# attenuverter_7-24-22.net
KiCad netlist of a schematic drawn in EAGLE
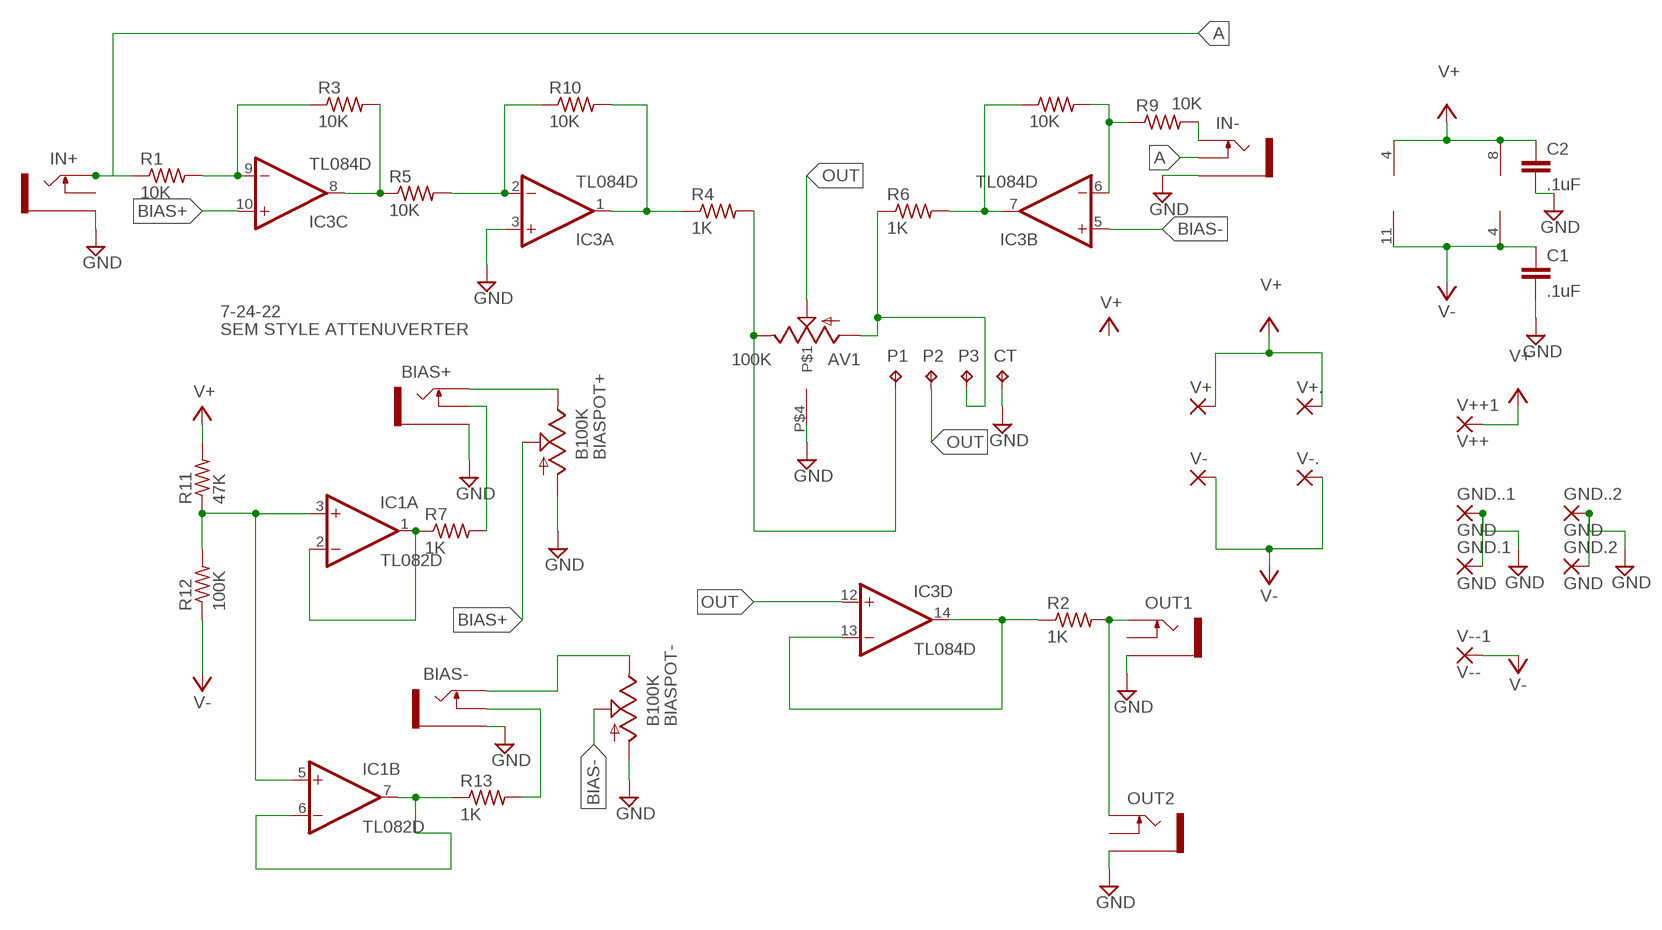
[diagram p0: schematic, sheet 1]

(export (version "E")
  (design (tool "Eeschema 10.0.6"))
  (components
    (comp (ref "AV1")
      (value "100K")
      (footprint "eagle-import:ALPSCENTERTAP")
      (libsource (lib "eagle-import") (part "ALPSRK11K114"))
    )
    (comp (ref "BIAS+")
      (value "THONKICONNOLD")
      (footprint "eagle-import:THONKICONN")
      (libsource (lib "eagle-import") (part "THONKICONNOLD"))
    )
    (comp (ref "BIAS-")
      (value "THONKICONNOLD")
      (footprint "eagle-import:THONKICONN")
      (libsource (lib "eagle-import") (part "THONKICONNOLD"))
    )
    (comp (ref "BIASPOT+")
      (value "B100K")
      (footprint "eagle-import:9MM_SNAP-IN_POT")
      (libsource (lib "eagle-import") (part "9MM_SNAP-IN_POT_"))
    )
    (comp (ref "BIASPOT-")
      (value "B100K")
      (footprint "eagle-import:9MM_SNAP-IN_POT")
      (libsource (lib "eagle-import") (part "9MM_SNAP-IN_POT_"))
    )
    (comp (ref "C1")
      (value ".1uF")
      (footprint "eagle-import:C5B3.5")
      (libsource (lib "eagle-import") (part "C5/3.5"))
    )
    (comp (ref "C2")
      (value ".1uF")
      (footprint "eagle-import:C5B3.5")
      (libsource (lib "eagle-import") (part "C5/3.5"))
    )
    (comp (ref "CT")
      (value "TPPAD1-13")
      (footprint "eagle-import:P1-13")
      (libsource (lib "eagle-import") (part "TPPAD1-13"))
    )
    (comp (ref "GND..1")
      (value "GND")
      (footprint "eagle-import:1,6_0,8")
      (libsource (lib "eagle-import") (part "1,6/0,8"))
    )
    (comp (ref "GND..2")
      (value "GND")
      (footprint "eagle-import:1,6_0,8")
      (libsource (lib "eagle-import") (part "1,6/0,8"))
    )
    (comp (ref "GND.1")
      (value "GND")
      (footprint "eagle-import:1,6_0,8")
      (libsource (lib "eagle-import") (part "1,6/0,8"))
    )
    (comp (ref "GND.2")
      (value "GND")
      (footprint "eagle-import:1,6_0,8")
      (libsource (lib "eagle-import") (part "1,6/0,8"))
    )
    (comp (ref "IC1")
      (value "TL082D")
      (footprint "eagle-import:SO08")
      (libsource (lib "eagle-import") (part "TL082D"))
    )
    (comp (ref "IC3")
      (value "TL084D")
      (footprint "eagle-import:SO14")
      (libsource (lib "eagle-import") (part "TL084D"))
    )
    (comp (ref "IN+")
      (value "THONKICONNOLD")
      (footprint "eagle-import:THONKICONN")
      (libsource (lib "eagle-import") (part "THONKICONNOLD"))
    )
    (comp (ref "IN-")
      (value "THONKICONNOLD")
      (footprint "eagle-import:THONKICONN")
      (libsource (lib "eagle-import") (part "THONKICONNOLD"))
    )
    (comp (ref "OUT1")
      (value "THONKICONNOLD")
      (footprint "eagle-import:THONKICONN")
      (libsource (lib "eagle-import") (part "THONKICONNOLD"))
    )
    (comp (ref "OUT2")
      (value "THONKICONNOLD")
      (footprint "eagle-import:THONKICONN")
      (libsource (lib "eagle-import") (part "THONKICONNOLD"))
    )
    (comp (ref "P1")
      (value "TPPAD1-13")
      (footprint "eagle-import:P1-13")
      (libsource (lib "eagle-import") (part "TPPAD1-13"))
    )
    (comp (ref "P2")
      (value "TPPAD1-13")
      (footprint "eagle-import:P1-13")
      (libsource (lib "eagle-import") (part "TPPAD1-13"))
    )
    (comp (ref "P3")
      (value "TPPAD1-13")
      (footprint "eagle-import:P1-13")
      (libsource (lib "eagle-import") (part "TPPAD1-13"))
    )
    (comp (ref "R1")
      (value "10K")
      (footprint "eagle-import:0204_7")
      (libsource (lib "eagle-import") (part "R-US_0204/7"))
    )
    (comp (ref "R2")
      (value "1K")
      (footprint "eagle-import:0204_7")
      (libsource (lib "eagle-import") (part "R-US_0204/7"))
    )
    (comp (ref "R3")
      (value "10K")
      (footprint "eagle-import:0204_7")
      (libsource (lib "eagle-import") (part "R-US_0204/7"))
    )
    (comp (ref "R4")
      (value "1K")
      (footprint "eagle-import:0204_7")
      (libsource (lib "eagle-import") (part "R-US_0204/7"))
    )
    (comp (ref "R5")
      (value "10K")
      (footprint "eagle-import:0204_7")
      (libsource (lib "eagle-import") (part "R-US_0204/7"))
    )
    (comp (ref "R6")
      (value "1K")
      (footprint "eagle-import:0204_7")
      (libsource (lib "eagle-import") (part "R-US_0204/7"))
    )
    (comp (ref "R7")
      (value "1K")
      (footprint "eagle-import:0204_7")
      (libsource (lib "eagle-import") (part "R-US_0204/7"))
    )
    (comp (ref "R8")
      (value "10K")
      (footprint "eagle-import:0204_7")
      (libsource (lib "eagle-import") (part "R-US_0204/7"))
    )
    (comp (ref "R9")
      (value "10K")
      (footprint "eagle-import:0204_7")
      (libsource (lib "eagle-import") (part "R-US_0204/7"))
    )
    (comp (ref "R10")
      (value "10K")
      (footprint "eagle-import:0204_7")
      (libsource (lib "eagle-import") (part "R-US_0204/7"))
    )
    (comp (ref "R11")
      (value "47K")
      (footprint "eagle-import:0204_7")
      (libsource (lib "eagle-import") (part "R-US_0204/7"))
    )
    (comp (ref "R12")
      (value "100K")
      (footprint "eagle-import:0204_7")
      (libsource (lib "eagle-import") (part "R-US_0204/7"))
    )
    (comp (ref "R13")
      (value "1K")
      (footprint "eagle-import:0204_7")
      (libsource (lib "eagle-import") (part "R-US_0204/7"))
    )
    (comp (ref "V+")
      (value "WIREPAD2,54/1,1")
      (footprint "eagle-import:2,54_1,1")
      (libsource (lib "eagle-import") (part "WIREPAD2,54/1,1"))
    )
    (comp (ref "V++1")
      (value "V++")
      (footprint "eagle-import:1,6_0,8")
      (libsource (lib "eagle-import") (part "1,6/0,8"))
    )
    (comp (ref "V+.")
      (value "WIREPAD2,54/1,1")
      (footprint "eagle-import:2,54_1,1")
      (libsource (lib "eagle-import") (part "WIREPAD2,54/1,1"))
    )
    (comp (ref "V-")
      (value "WIREPAD2,54/1,1")
      (footprint "eagle-import:2,54_1,1")
      (libsource (lib "eagle-import") (part "WIREPAD2,54/1,1"))
    )
    (comp (ref "V--1")
      (value "V--")
      (footprint "eagle-import:1,6_0,8")
      (libsource (lib "eagle-import") (part "1,6/0,8"))
    )
    (comp (ref "V-.")
      (value "WIREPAD2,54/1,1")
      (footprint "eagle-import:2,54_1,1")
      (libsource (lib "eagle-import") (part "WIREPAD2,54/1,1"))
    )
  )
  (nets
    (net (code "1") (name "A") (class "Default")
      (node (ref "IN+") (pin "P$3_TIP") (pinfunction "TIP_P$3_TIP") (pintype "passive"))
      (node (ref "IN-") (pin "P$2_SWITCH") (pinfunction "SWITCH_P$2_SWITCH") (pintype "passive"))
      (node (ref "R1") (pin "1") (pinfunction "1_1") (pintype "passive"))
    )
    (net (code "2") (name "BIAS+") (class "Default")
      (node (ref "BIASPOT+") (pin "2") (pinfunction "S_2") (pintype "passive"))
      (node (ref "IC3") (pin "10") (pinfunction "+IN_10") (pintype "input"))
    )
    (net (code "3") (name "BIAS-") (class "Default")
      (node (ref "BIASPOT-") (pin "2") (pinfunction "S_2") (pintype "passive"))
      (node (ref "IC3") (pin "5") (pinfunction "+IN_5") (pintype "input"))
    )
    (net (code "4") (name "GND") (class "Default")
      (node (ref "AV1") (pin "P$4") (pinfunction "P$1_P$4") (pintype "passive"))
      (node (ref "BIAS+") (pin "P$1_SLEEVE") (pinfunction "SLEEVE_P$1_SLEEVE") (pintype "passive"))
      (node (ref "BIAS-") (pin "P$1_SLEEVE") (pinfunction "SLEEVE_P$1_SLEEVE") (pintype "passive"))
      (node (ref "BIASPOT+") (pin "1") (pinfunction "A_1") (pintype "passive"))
      (node (ref "BIASPOT-") (pin "1") (pinfunction "A_1") (pintype "passive"))
      (node (ref "C1") (pin "2") (pinfunction "2_2") (pintype "passive"))
      (node (ref "C2") (pin "2") (pinfunction "2_2") (pintype "passive"))
      (node (ref "CT") (pin "TP") (pinfunction "TP_TP") (pintype "input"))
      (node (ref "GND..1") (pin "1") (pinfunction "P_1") (pintype "passive"))
      (node (ref "GND..2") (pin "1") (pinfunction "P_1") (pintype "passive"))
      (node (ref "GND.1") (pin "1") (pinfunction "P_1") (pintype "passive"))
      (node (ref "GND.2") (pin "1") (pinfunction "P_1") (pintype "passive"))
      (node (ref "IC3") (pin "3") (pinfunction "+IN_3") (pintype "input"))
      (node (ref "IN+") (pin "P$1_SLEEVE") (pinfunction "SLEEVE_P$1_SLEEVE") (pintype "passive"))
      (node (ref "IN-") (pin "P$1_SLEEVE") (pinfunction "SLEEVE_P$1_SLEEVE") (pintype "passive"))
      (node (ref "OUT1") (pin "P$1_SLEEVE") (pinfunction "SLEEVE_P$1_SLEEVE") (pintype "passive"))
      (node (ref "OUT2") (pin "P$1_SLEEVE") (pinfunction "SLEEVE_P$1_SLEEVE") (pintype "passive"))
    )
    (net (code "5") (name "Net-(AV1-HIGH)") (class "Default")
      (node (ref "AV1") (pin "P$1") (pinfunction "HIGH_P$1") (pintype "passive"))
      (node (ref "P1") (pin "TP") (pinfunction "TP_TP") (pintype "input"))
      (node (ref "R4") (pin "2") (pinfunction "2_2") (pintype "passive"))
    )
    (net (code "6") (name "Net-(AV1-LOW)") (class "Default")
      (node (ref "AV1") (pin "P$3") (pinfunction "LOW_P$3") (pintype "passive"))
      (node (ref "P3") (pin "TP") (pinfunction "TP_TP") (pintype "input"))
      (node (ref "R6") (pin "1") (pinfunction "1_1") (pintype "passive"))
    )
    (net (code "7") (name "Net-(BIAS+-SWITCH)") (class "Default")
      (node (ref "BIAS+") (pin "P$2_SWITCH") (pinfunction "SWITCH_P$2_SWITCH") (pintype "passive"))
      (node (ref "R7") (pin "2") (pinfunction "2_2") (pintype "passive"))
    )
    (net (code "8") (name "Net-(BIAS+-TIP)") (class "Default")
      (node (ref "BIAS+") (pin "P$3_TIP") (pinfunction "TIP_P$3_TIP") (pintype "passive"))
      (node (ref "BIASPOT+") (pin "3") (pinfunction "E_3") (pintype "passive"))
    )
    (net (code "9") (name "Net-(BIAS--SWITCH)") (class "Default")
      (node (ref "BIAS-") (pin "P$2_SWITCH") (pinfunction "SWITCH_P$2_SWITCH") (pintype "passive"))
      (node (ref "R13") (pin "2") (pinfunction "2_2") (pintype "passive"))
    )
    (net (code "10") (name "Net-(BIAS--TIP)") (class "Default")
      (node (ref "BIAS-") (pin "P$3_TIP") (pinfunction "TIP_P$3_TIP") (pintype "passive"))
      (node (ref "BIASPOT-") (pin "3") (pinfunction "E_3") (pintype "passive"))
    )
    (net (code "11") (name "Net-(IC1A-+IN)") (class "Default")
      (node (ref "IC1") (pin "3") (pinfunction "+IN_3") (pintype "input"))
      (node (ref "IC1") (pin "5") (pinfunction "+IN_5") (pintype "input"))
      (node (ref "R11") (pin "1") (pinfunction "1_1") (pintype "passive"))
      (node (ref "R12") (pin "2") (pinfunction "2_2") (pintype "passive"))
    )
    (net (code "12") (name "Net-(IC1A--IN)") (class "Default")
      (node (ref "IC1") (pin "1") (pinfunction "OUT_1") (pintype "output"))
      (node (ref "IC1") (pin "2") (pinfunction "-IN_2") (pintype "input"))
      (node (ref "R7") (pin "1") (pinfunction "1_1") (pintype "passive"))
    )
    (net (code "13") (name "Net-(IC1B--IN)") (class "Default")
      (node (ref "IC1") (pin "6") (pinfunction "-IN_6") (pintype "input"))
      (node (ref "IC1") (pin "7") (pinfunction "OUT_7") (pintype "output"))
      (node (ref "R13") (pin "1") (pinfunction "1_1") (pintype "passive"))
    )
    (net (code "14") (name "Net-(IC3A--IN)") (class "Default")
      (node (ref "IC3") (pin "2") (pinfunction "-IN_2") (pintype "input"))
      (node (ref "R10") (pin "1") (pinfunction "1_1") (pintype "passive"))
      (node (ref "R5") (pin "2") (pinfunction "2_2") (pintype "passive"))
    )
    (net (code "15") (name "Net-(IC3A-OUT)") (class "Default")
      (node (ref "IC3") (pin "1") (pinfunction "OUT_1") (pintype "output"))
      (node (ref "R10") (pin "2") (pinfunction "2_2") (pintype "passive"))
      (node (ref "R4") (pin "1") (pinfunction "1_1") (pintype "passive"))
    )
    (net (code "16") (name "Net-(IC3B--IN)") (class "Default")
      (node (ref "IC3") (pin "6") (pinfunction "-IN_6") (pintype "input"))
      (node (ref "R8") (pin "2") (pinfunction "2_2") (pintype "passive"))
      (node (ref "R9") (pin "1") (pinfunction "1_1") (pintype "passive"))
    )
    (net (code "17") (name "Net-(IC3B-OUT)") (class "Default")
      (node (ref "IC3") (pin "7") (pinfunction "OUT_7") (pintype "output"))
      (node (ref "R6") (pin "2") (pinfunction "2_2") (pintype "passive"))
      (node (ref "R8") (pin "1") (pinfunction "1_1") (pintype "passive"))
    )
    (net (code "18") (name "Net-(IC3C--IN)") (class "Default")
      (node (ref "IC3") (pin "9") (pinfunction "-IN_9") (pintype "input"))
      (node (ref "R1") (pin "2") (pinfunction "2_2") (pintype "passive"))
      (node (ref "R3") (pin "1") (pinfunction "1_1") (pintype "passive"))
    )
    (net (code "19") (name "Net-(IC3C-OUT)") (class "Default")
      (node (ref "IC3") (pin "8") (pinfunction "OUT_8") (pintype "output"))
      (node (ref "R3") (pin "2") (pinfunction "2_2") (pintype "passive"))
      (node (ref "R5") (pin "1") (pinfunction "1_1") (pintype "passive"))
    )
    (net (code "20") (name "Net-(IC3D--IN)") (class "Default")
      (node (ref "IC3") (pin "13") (pinfunction "-IN_13") (pintype "input"))
      (node (ref "IC3") (pin "14") (pinfunction "OUT_14") (pintype "output"))
      (node (ref "R2") (pin "1") (pinfunction "1_1") (pintype "passive"))
    )
    (net (code "21") (name "Net-(IN--TIP)") (class "Default")
      (node (ref "IN-") (pin "P$3_TIP") (pinfunction "TIP_P$3_TIP") (pintype "passive"))
      (node (ref "R9") (pin "2") (pinfunction "2_2") (pintype "passive"))
    )
    (net (code "22") (name "Net-(OUT1-TIP)") (class "Default")
      (node (ref "OUT1") (pin "P$3_TIP") (pinfunction "TIP_P$3_TIP") (pintype "passive"))
      (node (ref "OUT2") (pin "P$3_TIP") (pinfunction "TIP_P$3_TIP") (pintype "passive"))
      (node (ref "R2") (pin "2") (pinfunction "2_2") (pintype "passive"))
    )
    (net (code "23") (name "OUT") (class "Default")
      (node (ref "AV1") (pin "P$2") (pinfunction "WIPER_P$2") (pintype "passive"))
      (node (ref "IC3") (pin "12") (pinfunction "+IN_12") (pintype "input"))
      (node (ref "P2") (pin "TP") (pinfunction "TP_TP") (pintype "input"))
    )
    (net (code "24") (name "V+") (class "Default")
      (node (ref "C2") (pin "1") (pinfunction "1_1") (pintype "passive"))
      (node (ref "IC1") (pin "8") (pinfunction "V+_8") (pintype "power_in"))
      (node (ref "IC3") (pin "4") (pinfunction "V+_4") (pintype "power_in"))
      (node (ref "R11") (pin "2") (pinfunction "2_2") (pintype "passive"))
      (node (ref "V+") (pin "1") (pinfunction "P_1") (pintype "passive"))
      (node (ref "V++1") (pin "1") (pinfunction "P_1") (pintype "passive"))
      (node (ref "V+.") (pin "1") (pinfunction "P_1") (pintype "passive"))
    )
    (net (code "25") (name "V-") (class "Default")
      (node (ref "C1") (pin "1") (pinfunction "1_1") (pintype "passive"))
      (node (ref "IC1") (pin "4") (pinfunction "V-_4") (pintype "power_in"))
      (node (ref "IC3") (pin "11") (pinfunction "V-_11") (pintype "power_in"))
      (node (ref "R12") (pin "1") (pinfunction "1_1") (pintype "passive"))
      (node (ref "V-") (pin "1") (pinfunction "P_1") (pintype "passive"))
      (node (ref "V--1") (pin "1") (pinfunction "P_1") (pintype "passive"))
      (node (ref "V-.") (pin "1") (pinfunction "P_1") (pintype "passive"))
    )
    (net (code "26") (name "unconnected-(IN+-SWITCH-PadP$2_SWITCH)") (class "Default")
      (node (ref "IN+") (pin "P$2_SWITCH") (pinfunction "SWITCH_P$2_SWITCH") (pintype "passive"))
    )
    (net (code "27") (name "unconnected-(OUT1-SWITCH-PadP$2_SWITCH)") (class "Default")
      (node (ref "OUT1") (pin "P$2_SWITCH") (pinfunction "SWITCH_P$2_SWITCH") (pintype "passive"))
    )
    (net (code "28") (name "unconnected-(OUT2-SWITCH-PadP$2_SWITCH)") (class "Default")
      (node (ref "OUT2") (pin "P$2_SWITCH") (pinfunction "SWITCH_P$2_SWITCH") (pintype "passive"))
    )
  )
)
